# AFWS_V3_1_Slave.net
KiCad netlist of a schematic drawn in Altium Designer
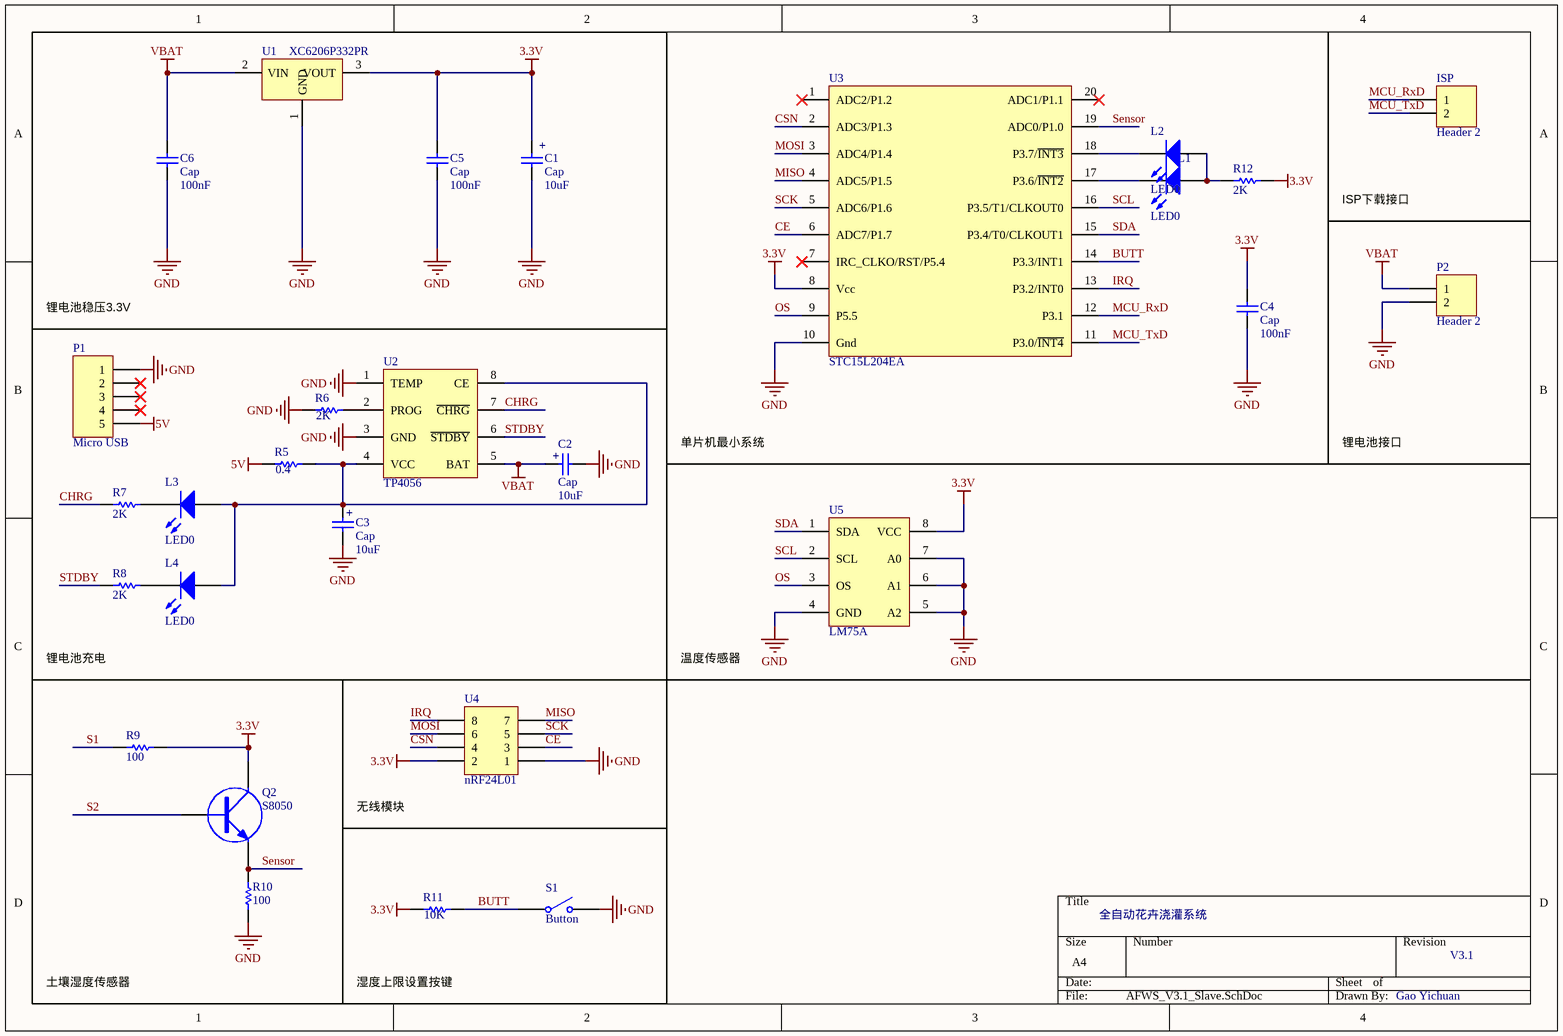
[diagram p0: AFWS_V3.1_Slave.SchDoc]

(export (version "E")
  (design (tool "Eeschema 10.0.6"))
  (components
    (comp (ref "C1")
      (value "Cap")
      (footprint "RESC6332")
      (description "Capacitor")
      (fields (field (name "ALTIUM_VALUE") "10uF") (field (name "PUBLISHER") "Altium Limited"))
      (libsource (lib "Miscellaneous Devices") (part "Cap"))
    )
    (comp (ref "C2")
      (value "Cap")
      (footprint "RESC6332")
      (description "Capacitor")
      (fields (field (name "ALTIUM_VALUE") "10uF") (field (name "PUBLISHER") "Altium Limited"))
      (libsource (lib "Miscellaneous Devices") (part "Cap"))
    )
    (comp (ref "C3")
      (value "Cap")
      (footprint "RESC6332")
      (description "Capacitor")
      (fields (field (name "ALTIUM_VALUE") "10uF") (field (name "PUBLISHER") "Altium Limited"))
      (libsource (lib "Miscellaneous Devices") (part "Cap"))
    )
    (comp (ref "C4")
      (value "Cap")
      (footprint "0805")
      (description "Capacitor")
      (fields (field (name "ALTIUM_VALUE") "100nF") (field (name "PUBLISHER") "Altium Limited"))
      (libsource (lib "Miscellaneous Devices") (part "Cap"))
    )
    (comp (ref "C5")
      (value "Cap")
      (footprint "0805")
      (description "Capacitor")
      (fields (field (name "ALTIUM_VALUE") "100nF") (field (name "PUBLISHER") "Altium Limited"))
      (libsource (lib "Miscellaneous Devices") (part "Cap"))
    )
    (comp (ref "C6")
      (value "Cap")
      (footprint "0805")
      (description "Capacitor")
      (fields (field (name "ALTIUM_VALUE") "100nF") (field (name "PUBLISHER") "Altium Limited"))
      (libsource (lib "Miscellaneous Devices") (part "Cap"))
    )
    (comp (ref "ISP")
      (value "Header 2")
      (footprint "HDR1X2")
      (description "Header, 2-Pin")
      (fields (field (name "PUBLISHER") "Altium Limited"))
      (libsource (lib "Miscellaneous Connectors") (part "Header 2"))
    )
    (comp (ref "L1")
      (value "LED0")
      (footprint "0805")
      (description "Typical INFRARED GaAs LED")
      (fields (field (name "PUBLISHER") "Altium Limited"))
      (libsource (lib "Miscellaneous Devices") (part "LED0"))
    )
    (comp (ref "L2")
      (value "LED0")
      (footprint "0805")
      (description "Typical INFRARED GaAs LED")
      (fields (field (name "PUBLISHER") "Altium Limited"))
      (libsource (lib "Miscellaneous Devices") (part "LED0"))
    )
    (comp (ref "L3")
      (value "LED0")
      (footprint "0805")
      (description "Typical INFRARED GaAs LED")
      (fields (field (name "PUBLISHER") "Altium Limited"))
      (libsource (lib "Miscellaneous Devices") (part "LED0"))
    )
    (comp (ref "L4")
      (value "LED0")
      (footprint "0805")
      (description "Typical INFRARED GaAs LED")
      (fields (field (name "PUBLISHER") "Altium Limited"))
      (libsource (lib "Miscellaneous Devices") (part "LED0"))
    )
    (comp (ref "P1")
      (value "Micro USB")
      (footprint "Micro_USB")
      (description "Header, 5-Pin")
      (fields (field (name "PUBLISHER") "Altium Limited"))
      (libsource (lib "Miscellaneous Connectors") (part "Header 5"))
    )
    (comp (ref "P2")
      (value "Header 2")
      (footprint "HDR1X2")
      (description "Header, 2-Pin")
      (fields (field (name "PUBLISHER") "Altium Limited"))
      (libsource (lib "Miscellaneous Connectors") (part "Header 2"))
    )
    (comp (ref "Q2")
      (value "S8050")
      (footprint "SOT-23")
      (description "NPN Transistor")
      (libsource (lib "杂元件库") (part "NPN"))
    )
    (comp (ref "R5")
      (value "0.4")
      (footprint "1206")
      (description "Resistor")
      (fields (field (name "Comment") "Res1") (field (name "PUBLISHER") "Altium Limited"))
      (libsource (lib "Miscellaneous Devices") (part "Res1"))
    )
    (comp (ref "R6")
      (value "2K")
      (footprint "0805")
      (description "Resistor")
      (fields (field (name "Comment") "Res1") (field (name "PUBLISHER") "Altium Limited"))
      (libsource (lib "Miscellaneous Devices") (part "Res1"))
    )
    (comp (ref "R7")
      (value "2K")
      (footprint "0805")
      (description "Resistor")
      (fields (field (name "Comment") "Res1") (field (name "PUBLISHER") "Altium Limited"))
      (libsource (lib "Miscellaneous Devices") (part "Res1"))
    )
    (comp (ref "R8")
      (value "2K")
      (footprint "0805")
      (description "Resistor")
      (fields (field (name "Comment") "Res1") (field (name "PUBLISHER") "Altium Limited"))
      (libsource (lib "Miscellaneous Devices") (part "Res1"))
    )
    (comp (ref "R9")
      (value "100")
      (footprint "0805")
      (description "Resistor")
      (fields (field (name "Comment") "Res1") (field (name "PUBLISHER") "Altium Limited"))
      (libsource (lib "Miscellaneous Devices") (part "Res1"))
    )
    (comp (ref "R10")
      (value "100")
      (footprint "0805")
      (description "Resistor")
      (fields (field (name "Comment") "Res1") (field (name "PUBLISHER") "Altium Limited"))
      (libsource (lib "Miscellaneous Devices") (part "Res1"))
    )
    (comp (ref "R11")
      (value "10K")
      (footprint "0805")
      (description "Resistor")
      (fields (field (name "Comment") "Res1") (field (name "PUBLISHER") "Altium Limited"))
      (libsource (lib "Miscellaneous Devices") (part "Res1"))
    )
    (comp (ref "R12")
      (value "2K")
      (footprint "0805")
      (description "Resistor")
      (fields (field (name "Comment") "Res1") (field (name "PUBLISHER") "Altium Limited"))
      (libsource (lib "Miscellaneous Devices") (part "Res1"))
    )
    (comp (ref "S1")
      (value "Button")
      (footprint "Button2")
      (description "Single-Pole, Single-Throw Switch")
      (fields (field (name "PUBLISHER") "Altium Limited"))
      (libsource (lib "Miscellaneous Devices") (part "SW-SPST"))
    )
    (comp (ref "U1") (value "XC6206P332PR") (footprint "SOT-89") (libsource (lib "XC6206") (part "XC6206")))
    (comp (ref "U2") (value "TP4056") (footprint "SO-08") (libsource (lib "TP4056") (part "TP4056")))
    (comp (ref "U3")
      (value "STC15L204EA")
      (footprint "SOL-20")
      (libsource (lib "STC15L204EA") (part "STC15L204EA"))
    )
    (comp (ref "U4")
      (value "nRF24L01")
      (footprint "HDR2X4")
      (description "Header, 4-Pin, Dual row")
      (fields (field (name "PUBLISHER") "Altium Limited"))
      (libsource (lib "Miscellaneous Connectors") (part "Header 4X2"))
    )
    (comp (ref "U5") (value "LM75A") (footprint "SO-08") (libsource (lib "LM75A") (part "LM75A")))
  )
  (nets
    (net (code "1") (name "/BUTT") (class "Default")
      (node (ref "R11") (pin "2") (pinfunction "2_2") (pintype "passive"))
      (node (ref "S1") (pin "1") (pinfunction "COMMON_1") (pintype "passive"))
      (node (ref "U3") (pin "14") (pinfunction "P3.3/INT1_14") (pintype "passive"))
    )
    (net (code "2") (name "/CE") (class "Default")
      (node (ref "U3") (pin "6") (pinfunction "ADC7/P1.7_6") (pintype "passive"))
      (node (ref "U4") (pin "3") (pinfunction "3_3") (pintype "passive"))
    )
    (net (code "3") (name "/CHRG") (class "Default")
      (node (ref "R7") (pin "2") (pinfunction "2_2") (pintype "passive"))
      (node (ref "U2") (pin "7") (pinfunction "~{CHRG}_7") (pintype "passive"))
    )
    (net (code "4") (name "/CSN") (class "Default")
      (node (ref "U3") (pin "2") (pinfunction "ADC3/P1.3_2") (pintype "passive"))
      (node (ref "U4") (pin "4") (pinfunction "4_4") (pintype "passive"))
    )
    (net (code "5") (name "/IRQ") (class "Default")
      (node (ref "U3") (pin "13") (pinfunction "P3.2/INT0_13") (pintype "passive"))
      (node (ref "U4") (pin "8") (pinfunction "8_8") (pintype "passive"))
    )
    (net (code "6") (name "/MCU_RxD") (class "Default")
      (node (ref "ISP") (pin "1") (pinfunction "1_1") (pintype "passive"))
      (node (ref "U3") (pin "12") (pinfunction "P3.1_12") (pintype "passive"))
    )
    (net (code "7") (name "/MCU_TxD") (class "Default")
      (node (ref "ISP") (pin "2") (pinfunction "2_2") (pintype "passive"))
      (node (ref "U3") (pin "11") (pinfunction "P3.0/~{INT4}_11") (pintype "passive"))
    )
    (net (code "8") (name "/MISO") (class "Default")
      (node (ref "U3") (pin "4") (pinfunction "ADC5/P1.5_4") (pintype "passive"))
      (node (ref "U4") (pin "7") (pinfunction "7_7") (pintype "passive"))
    )
    (net (code "9") (name "/MOSI") (class "Default")
      (node (ref "U3") (pin "3") (pinfunction "ADC4/P1.4_3") (pintype "passive"))
      (node (ref "U4") (pin "6") (pinfunction "6_6") (pintype "passive"))
    )
    (net (code "10") (name "/OS") (class "Default")
      (node (ref "U3") (pin "9") (pinfunction "P5.5_9") (pintype "passive"))
      (node (ref "U5") (pin "3") (pinfunction "OS_3") (pintype "passive"))
    )
    (net (code "11") (name "/S1") (class "Default")
      (node (ref "R9") (pin "2") (pinfunction "2_2") (pintype "passive"))
    )
    (net (code "12") (name "/S2") (class "Default")
      (node (ref "Q2") (pin "1") (pinfunction "B_1") (pintype "passive"))
    )
    (net (code "13") (name "/SCK") (class "Default")
      (node (ref "U3") (pin "5") (pinfunction "ADC6/P1.6_5") (pintype "passive"))
      (node (ref "U4") (pin "5") (pinfunction "5_5") (pintype "passive"))
    )
    (net (code "14") (name "/SCL") (class "Default")
      (node (ref "U3") (pin "16") (pinfunction "P3.5/T1/CLKOUT0_16") (pintype "passive"))
      (node (ref "U5") (pin "2") (pinfunction "SCL_2") (pintype "passive"))
    )
    (net (code "15") (name "/SDA") (class "Default")
      (node (ref "U3") (pin "15") (pinfunction "P3.4/T0/CLKOUT1_15") (pintype "passive"))
      (node (ref "U5") (pin "1") (pinfunction "SDA_1") (pintype "passive"))
    )
    (net (code "16") (name "/STDBY") (class "Default")
      (node (ref "R8") (pin "2") (pinfunction "2_2") (pintype "passive"))
      (node (ref "U2") (pin "6") (pinfunction "~{STDBY}_6") (pintype "passive"))
    )
    (net (code "17") (name "/Sensor") (class "Default")
      (node (ref "Q2") (pin "3") (pinfunction "E_3") (pintype "passive"))
      (node (ref "R10") (pin "1") (pinfunction "1_1") (pintype "passive"))
      (node (ref "U3") (pin "19") (pinfunction "ADC0/P1.0_19") (pintype "passive"))
    )
    (net (code "18") (name "3.3V") (class "Default")
      (node (ref "C1") (pin "2") (pinfunction "2_2") (pintype "passive"))
      (node (ref "C4") (pin "2") (pinfunction "2_2") (pintype "passive"))
      (node (ref "C5") (pin "2") (pinfunction "2_2") (pintype "passive"))
      (node (ref "Q2") (pin "2") (pinfunction "C_2") (pintype "passive"))
      (node (ref "R11") (pin "1") (pinfunction "1_1") (pintype "passive"))
      (node (ref "R12") (pin "1") (pinfunction "1_1") (pintype "passive"))
      (node (ref "R9") (pin "1") (pinfunction "1_1") (pintype "passive"))
      (node (ref "U1") (pin "3") (pinfunction "VOUT_3") (pintype "passive"))
      (node (ref "U3") (pin "8") (pinfunction "Vcc_8") (pintype "passive"))
      (node (ref "U4") (pin "2") (pinfunction "2_2") (pintype "passive"))
      (node (ref "U5") (pin "8") (pinfunction "VCC_8") (pintype "passive"))
    )
    (net (code "19") (name "5V") (class "Default")
      (node (ref "P1") (pin "5") (pinfunction "5_5") (pintype "passive"))
      (node (ref "R5") (pin "1") (pinfunction "1_1") (pintype "passive"))
    )
    (net (code "20") (name "GND") (class "Default")
      (node (ref "C1") (pin "1") (pinfunction "1_1") (pintype "passive"))
      (node (ref "C2") (pin "2") (pinfunction "2_2") (pintype "passive"))
      (node (ref "C3") (pin "1") (pinfunction "1_1") (pintype "passive"))
      (node (ref "C4") (pin "1") (pinfunction "1_1") (pintype "passive"))
      (node (ref "C5") (pin "1") (pinfunction "1_1") (pintype "passive"))
      (node (ref "C6") (pin "1") (pinfunction "1_1") (pintype "passive"))
      (node (ref "P1") (pin "1") (pinfunction "1_1") (pintype "passive"))
      (node (ref "P2") (pin "2") (pinfunction "2_2") (pintype "passive"))
      (node (ref "R10") (pin "2") (pinfunction "2_2") (pintype "passive"))
      (node (ref "R6") (pin "1") (pinfunction "1_1") (pintype "passive"))
      (node (ref "S1") (pin "2") (pinfunction "NO_2") (pintype "passive"))
      (node (ref "U1") (pin "1") (pinfunction "GND_1") (pintype "passive"))
      (node (ref "U2") (pin "1") (pinfunction "TEMP_1") (pintype "passive"))
      (node (ref "U2") (pin "3") (pinfunction "GND_3") (pintype "passive"))
      (node (ref "U3") (pin "10") (pinfunction "Gnd_10") (pintype "passive"))
      (node (ref "U4") (pin "1") (pinfunction "1_1") (pintype "passive"))
      (node (ref "U5") (pin "4") (pinfunction "GND_4") (pintype "passive"))
      (node (ref "U5") (pin "5") (pinfunction "A2_5") (pintype "passive"))
      (node (ref "U5") (pin "6") (pinfunction "A1_6") (pintype "passive"))
      (node (ref "U5") (pin "7") (pinfunction "A0_7") (pintype "passive"))
    )
    (net (code "21") (name "Net-(L1-A)") (class "Default")
      (node (ref "L1") (pin "1") (pinfunction "A_1") (pintype "passive"))
      (node (ref "L2") (pin "1") (pinfunction "A_1") (pintype "passive"))
      (node (ref "R12") (pin "2") (pinfunction "2_2") (pintype "passive"))
    )
    (net (code "22") (name "Net-(L1-K)") (class "Default")
      (node (ref "L1") (pin "2") (pinfunction "K_2") (pintype "passive"))
      (node (ref "U3") (pin "17") (pinfunction "P3.6/~{INT2}_17") (pintype "passive"))
    )
    (net (code "23") (name "Net-(L2-K)") (class "Default")
      (node (ref "L2") (pin "2") (pinfunction "K_2") (pintype "passive"))
      (node (ref "U3") (pin "18") (pinfunction "P3.7/~{INT3}_18") (pintype "passive"))
    )
    (net (code "24") (name "Net-(L3-A)") (class "Default")
      (node (ref "C3") (pin "2") (pinfunction "2_2") (pintype "passive"))
      (node (ref "L3") (pin "1") (pinfunction "A_1") (pintype "passive"))
      (node (ref "L4") (pin "1") (pinfunction "A_1") (pintype "passive"))
      (node (ref "R5") (pin "2") (pinfunction "2_2") (pintype "passive"))
      (node (ref "U2") (pin "4") (pinfunction "VCC_4") (pintype "passive"))
      (node (ref "U2") (pin "8") (pinfunction "CE_8") (pintype "passive"))
    )
    (net (code "25") (name "Net-(L3-K)") (class "Default")
      (node (ref "L3") (pin "2") (pinfunction "K_2") (pintype "passive"))
      (node (ref "R7") (pin "1") (pinfunction "1_1") (pintype "passive"))
    )
    (net (code "26") (name "Net-(L4-K)") (class "Default")
      (node (ref "L4") (pin "2") (pinfunction "K_2") (pintype "passive"))
      (node (ref "R8") (pin "1") (pinfunction "1_1") (pintype "passive"))
    )
    (net (code "27") (name "Net-(U2-PROG)") (class "Default")
      (node (ref "R6") (pin "2") (pinfunction "2_2") (pintype "passive"))
      (node (ref "U2") (pin "2") (pinfunction "PROG_2") (pintype "passive"))
    )
    (net (code "28") (name "VBAT") (class "Default")
      (node (ref "C2") (pin "1") (pinfunction "1_1") (pintype "passive"))
      (node (ref "C6") (pin "2") (pinfunction "2_2") (pintype "passive"))
      (node (ref "P2") (pin "1") (pinfunction "1_1") (pintype "passive"))
      (node (ref "U1") (pin "2") (pinfunction "VIN_2") (pintype "passive"))
      (node (ref "U2") (pin "5") (pinfunction "BAT_5") (pintype "passive"))
    )
    (net (code "29") (name "unconnected-(P1-Pad2)") (class "Default")
      (node (ref "P1") (pin "2") (pinfunction "2_2") (pintype "passive+no_connect"))
    )
    (net (code "30") (name "unconnected-(P1-Pad3)") (class "Default")
      (node (ref "P1") (pin "3") (pinfunction "3_3") (pintype "passive+no_connect"))
    )
    (net (code "31") (name "unconnected-(P1-Pad4)") (class "Default")
      (node (ref "P1") (pin "4") (pinfunction "4_4") (pintype "passive+no_connect"))
    )
    (net (code "32") (name "unconnected-(U3-ADC1{slash}P1.1-Pad20)") (class "Default")
      (node (ref "U3") (pin "20") (pinfunction "ADC1/P1.1_20") (pintype "passive+no_connect"))
    )
    (net (code "33") (name "unconnected-(U3-ADC2{slash}P1.2-Pad1)") (class "Default")
      (node (ref "U3") (pin "1") (pinfunction "ADC2/P1.2_1") (pintype "passive+no_connect"))
    )
    (net (code "34") (name "unconnected-(U3-IRC_CLKO{slash}RST{slash}P5.4-Pad7)") (class "Default")
      (node (ref "U3") (pin "7") (pinfunction "IRC_CLKO/RST/P5.4_7") (pintype "passive+no_connect"))
    )
  )
)
